# RHS_FEST22-EV_Logic.net
KiCad netlist of a schematic drawn in Altium Designer
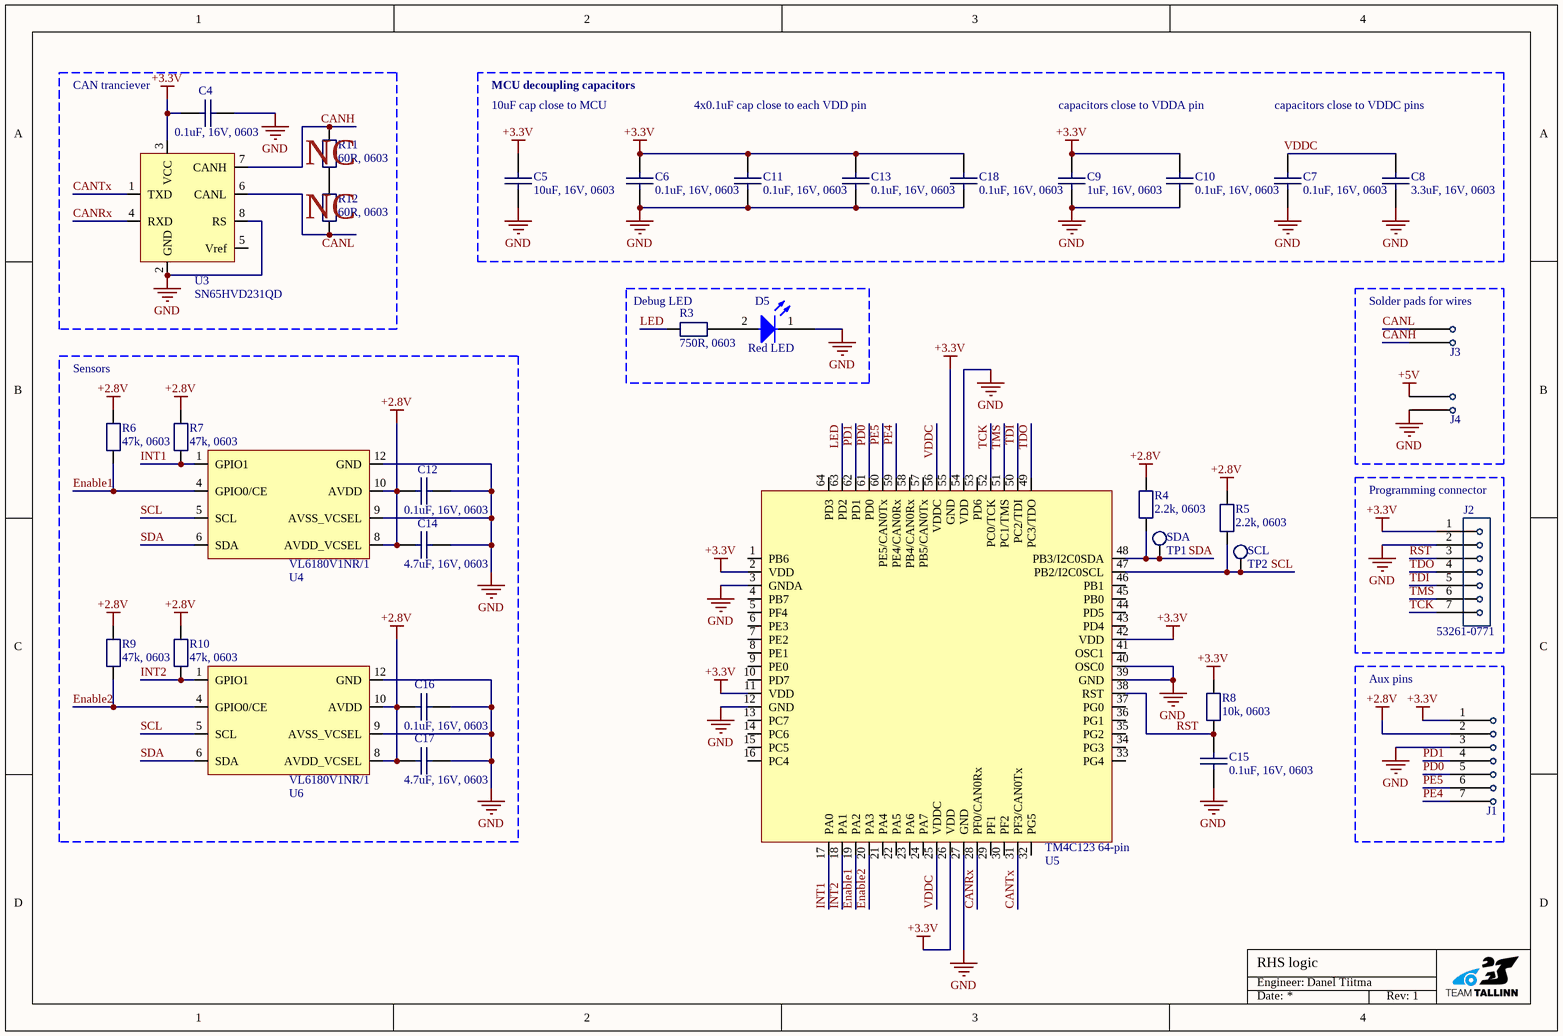
[diagram p0: RHS_FEST22-EV_Logic.SchDoc]

(export (version "E")
  (design (tool "Eeschema 10.0.6"))
  (components
    (comp (ref "C4")
      (value "0.1uF, 16V, 0603")
      (footprint "CAP [0603] 1608")
      (fields (field (name "MANUFACTURER") "MURATA"))
      (libsource (lib "RHS_FEST22-EV_Components") (part "Cap 0.1uF"))
    )
    (comp (ref "C5")
      (value "10uF, 16V, 0603")
      (footprint "CAP [0603] 1608")
      (fields (field (name "MANUFACTURER") "MURATA"))
      (libsource (lib "RHS_FEST22-EV_Components") (part "Cap 10uF"))
    )
    (comp (ref "C6")
      (value "0.1uF, 16V, 0603")
      (footprint "CAP [0603] 1608")
      (fields (field (name "MANUFACTURER") "MURATA"))
      (libsource (lib "RHS_FEST22-EV_Components") (part "Cap 0.1uF"))
    )
    (comp (ref "C7")
      (value "0.1uF, 16V, 0603")
      (footprint "CAP [0603] 1608")
      (fields (field (name "MANUFACTURER") "MURATA"))
      (libsource (lib "RHS_FEST22-EV_Components") (part "Cap 0.1uF"))
    )
    (comp (ref "C8")
      (value "3.3uF, 16V, 0603")
      (footprint "CAP [0603] 1608")
      (fields (field (name "MANUFACTURER") "TDK"))
      (libsource (lib "RHS_FEST22-EV_Components") (part "Cap 3.3uF"))
    )
    (comp (ref "C9")
      (value "1uF, 16V, 0603")
      (footprint "CAP [0603] 1608")
      (fields (field (name "MANUFACTURER") "MURATA"))
      (libsource (lib "RHS_FEST22-EV_Components") (part "Cap 1uF"))
    )
    (comp (ref "C10")
      (value "0.1uF, 16V, 0603")
      (footprint "CAP [0603] 1608")
      (fields (field (name "MANUFACTURER") "MURATA"))
      (libsource (lib "RHS_FEST22-EV_Components") (part "Cap 0.1uF"))
    )
    (comp (ref "C11")
      (value "0.1uF, 16V, 0603")
      (footprint "CAP [0603] 1608")
      (fields (field (name "MANUFACTURER") "MURATA"))
      (libsource (lib "RHS_FEST22-EV_Components") (part "Cap 0.1uF"))
    )
    (comp (ref "C12")
      (value "0.1uF, 16V, 0603")
      (footprint "CAP [0603] 1608")
      (fields (field (name "MANUFACTURER") "MURATA"))
      (libsource (lib "RHS_FEST22-EV_Components") (part "Cap 0.1uF"))
    )
    (comp (ref "C13")
      (value "0.1uF, 16V, 0603")
      (footprint "CAP [0603] 1608")
      (fields (field (name "MANUFACTURER") "MURATA"))
      (libsource (lib "RHS_FEST22-EV_Components") (part "Cap 0.1uF"))
    )
    (comp (ref "C14")
      (value "4.7uF, 16V, 0603")
      (footprint "FS_Footprints:CAP [0603] 1608")
      (fields (field (name "MANUFACTURER") "MURATA"))
      (libsource (lib "RHS_FEST22-EV_Components") (part "Cap 4.7uF"))
    )
    (comp (ref "C15")
      (value "0.1uF, 16V, 0603")
      (footprint "CAP [0603] 1608")
      (fields (field (name "MANUFACTURER") "MURATA"))
      (libsource (lib "RHS_FEST22-EV_Components") (part "Cap 0.1uF"))
    )
    (comp (ref "C16")
      (value "0.1uF, 16V, 0603")
      (footprint "CAP [0603] 1608")
      (fields (field (name "MANUFACTURER") "MURATA"))
      (libsource (lib "RHS_FEST22-EV_Components") (part "Cap 0.1uF"))
    )
    (comp (ref "C17")
      (value "4.7uF, 16V, 0603")
      (footprint "FS_Footprints:CAP [0603] 1608")
      (fields (field (name "MANUFACTURER") "MURATA"))
      (libsource (lib "RHS_FEST22-EV_Components") (part "Cap 4.7uF"))
    )
    (comp (ref "C18")
      (value "0.1uF, 16V, 0603")
      (footprint "CAP [0603] 1608")
      (fields (field (name "MANUFACTURER") "MURATA"))
      (libsource (lib "RHS_FEST22-EV_Components") (part "Cap 0.1uF"))
    )
    (comp (ref "D5")
      (value "Red LED")
      (footprint "LED [0603] 1608")
      (fields (field (name "MANUFACTURER") "KINGBRIGHT"))
      (libsource (lib "RHS_FEST22-EV_Components") (part "Red LED"))
    )
    (comp (ref "J1")
      (value "Wire connections_1")
      (footprint "Free pins")
      (description "Extra through holes")
      (libsource (lib "RHS_FEST22-EV_Components") (part "Wire connections_1"))
    )
    (comp (ref "J2")
      (value "53261-0771")
      (footprint "Molex 53261-0771")
      (description "Connector")
      (fields (field (name "MANUFACTURER") "Molex"))
      (libsource (lib "RHS_FEST22-EV_Components") (part "53261-0771"))
    )
    (comp (ref "J3")
      (value "Wire connections")
      (footprint "Wire pads")
      (libsource (lib "RHS_FEST22-EV_Components") (part "Wire connections"))
    )
    (comp (ref "J4")
      (value "Wire connections")
      (footprint "Wire pads")
      (libsource (lib "RHS_FEST22-EV_Components") (part "Wire connections"))
    )
    (comp (ref "R3")
      (value "750R, 0603")
      (footprint "RES [0603] 1608")
      (fields (field (name "MANUFACTURER") "YAGEO"))
      (libsource (lib "RHS_FEST22-EV_Components") (part "RES 750"))
    )
    (comp (ref "R4")
      (value "2.2k, 0603")
      (footprint "RES [0603] 1608")
      (fields (field (name "MANUFACTURER") "YAGEO"))
      (libsource (lib "RHS_FEST22-EV_Components") (part "Res 2.2k"))
    )
    (comp (ref "R5")
      (value "2.2k, 0603")
      (footprint "RES [0603] 1608")
      (fields (field (name "MANUFACTURER") "YAGEO"))
      (libsource (lib "RHS_FEST22-EV_Components") (part "Res 2.2k"))
    )
    (comp (ref "R6")
      (value "47k, 0603")
      (footprint "RES [0603] 1608")
      (fields (field (name "MANUFACTURER") "YAGEO"))
      (libsource (lib "RHS_FEST22-EV_Components") (part "Res 47k"))
    )
    (comp (ref "R7")
      (value "47k, 0603")
      (footprint "RES [0603] 1608")
      (fields (field (name "MANUFACTURER") "YAGEO"))
      (libsource (lib "RHS_FEST22-EV_Components") (part "Res 47k"))
    )
    (comp (ref "R8")
      (value "10k, 0603")
      (footprint "RES [0603] 1608")
      (fields (field (name "MANUFACTURER") "Yageo"))
      (libsource (lib "RHS_FEST22-EV_Components") (part "Res 10k"))
    )
    (comp (ref "R9")
      (value "47k, 0603")
      (footprint "RES [0603] 1608")
      (fields (field (name "MANUFACTURER") "YAGEO"))
      (libsource (lib "RHS_FEST22-EV_Components") (part "Res 47k"))
    )
    (comp (ref "R10")
      (value "47k, 0603")
      (footprint "RES [0603] 1608")
      (fields (field (name "MANUFACTURER") "YAGEO"))
      (libsource (lib "RHS_FEST22-EV_Components") (part "Res 47k"))
    )
    (comp (ref "R11")
      (value "60R, 0603")
      (footprint "FS_Footprints:RES [0603] 1608")
      (libsource (lib "FS_Components") (part "Resistor"))
    )
    (comp (ref "R12")
      (value "60R, 0603")
      (footprint "FS_Footprints:RES [0603] 1608")
      (libsource (lib "FS_Components") (part "Resistor"))
    )
    (comp (ref "TP1")
      (value "SDA")
      (footprint "FS_Footprints:Testpoint round 0.4mm")
      (libsource (lib "FS_Components") (part "Test Point"))
    )
    (comp (ref "TP2")
      (value "SCL")
      (footprint "FS_Footprints:Testpoint round 0.4mm")
      (libsource (lib "FS_Components") (part "Test Point"))
    )
    (comp (ref "U3")
      (value "SN65HVD231QD")
      (footprint "SOIC-8")
      (description "CAN tranciever")
      (fields (field (name "MANUFACTURER") "Texas Instruments"))
      (libsource (lib "RHS_FEST22-EV_Components") (part "SN65HVD231QD"))
    )
    (comp (ref "U4")
      (value "VL6180V1NR/1")
      (footprint "VL6180")
      (description "Time-of-Flight proximity sensor, 2.6V, 3V, Optical, RoHS")
      (fields (field (name "MANUFACTURER") "STMicroelectronics"))
      (libsource (lib "RHS_FEST22-EV_Components") (part "VL6180V1NR/1"))
    )
    (comp (ref "U5")
      (value "TM4C123 64-pin")
      (footprint "FS_Footprints:LQFP64")
      (description "MCU 32-Bit Tiva C ARM Cortex M4F RISC 256KB Flash 1.2V/3.3V 64-Pin LQFP Tray/Tube")
      (fields (field (name "MANUFACTURER") "Texas Instruments"))
      (libsource (lib "RHS_FEST22-EV_Components") (part "TM4C123 64-pin"))
    )
    (comp (ref "U6")
      (value "VL6180V1NR/1")
      (footprint "VL6180")
      (description "Time-of-Flight proximity sensor, 2.6V, 3V, Optical, RoHS")
      (fields (field (name "MANUFACTURER") "STMicroelectronics"))
      (libsource (lib "RHS_FEST22-EV_Components") (part "VL6180V1NR/1"))
    )
  )
  (nets
    (net (code "1") (name "+2.8V") (class "Default")
      (node (ref "C12") (pin "2") (pinfunction "2_2") (pintype "passive"))
      (node (ref "C14") (pin "2") (pinfunction "2_2") (pintype "passive"))
      (node (ref "C16") (pin "2") (pinfunction "2_2") (pintype "passive"))
      (node (ref "C17") (pin "2") (pinfunction "2_2") (pintype "passive"))
      (node (ref "J1") (pin "2") (pintype "passive"))
      (node (ref "R10") (pin "2") (pinfunction "2_2") (pintype "passive"))
      (node (ref "R4") (pin "2") (pinfunction "2_2") (pintype "passive"))
      (node (ref "R5") (pin "2") (pinfunction "2_2") (pintype "passive"))
      (node (ref "R6") (pin "2") (pinfunction "2_2") (pintype "passive"))
      (node (ref "R7") (pin "2") (pinfunction "2_2") (pintype "passive"))
      (node (ref "R9") (pin "2") (pinfunction "2_2") (pintype "passive"))
      (node (ref "U4") (pin "10") (pinfunction "AVDD_10") (pintype "passive"))
      (node (ref "U4") (pin "8") (pinfunction "AVDD_VCSEL_8") (pintype "passive"))
      (node (ref "U6") (pin "10") (pinfunction "AVDD_10") (pintype "passive"))
      (node (ref "U6") (pin "8") (pinfunction "AVDD_VCSEL_8") (pintype "passive"))
    )
    (net (code "2") (name "+3.3V") (class "Default")
      (node (ref "C10") (pin "1") (pinfunction "1_1") (pintype "passive"))
      (node (ref "C11") (pin "1") (pinfunction "1_1") (pintype "passive"))
      (node (ref "C13") (pin "1") (pinfunction "1_1") (pintype "passive"))
      (node (ref "C18") (pin "1") (pinfunction "1_1") (pintype "passive"))
      (node (ref "C4") (pin "2") (pinfunction "2_2") (pintype "passive"))
      (node (ref "C5") (pin "1") (pinfunction "1_1") (pintype "passive"))
      (node (ref "C6") (pin "2") (pinfunction "2_2") (pintype "passive"))
      (node (ref "C9") (pin "1") (pinfunction "1_1") (pintype "passive"))
      (node (ref "J1") (pin "1") (pintype "passive"))
      (node (ref "J2") (pin "1") (pinfunction "VCC_1") (pintype "passive"))
      (node (ref "R8") (pin "1") (pinfunction "1_1") (pintype "passive"))
      (node (ref "U3") (pin "3") (pinfunction "VCC_3") (pintype "passive"))
      (node (ref "U5") (pin "11") (pinfunction "VDD_11") (pintype "passive"))
      (node (ref "U5") (pin "2") (pinfunction "VDD_2") (pintype "passive"))
      (node (ref "U5") (pin "26") (pinfunction "VDD_26") (pintype "passive"))
      (node (ref "U5") (pin "42") (pinfunction "VDD_42") (pintype "passive"))
      (node (ref "U5") (pin "55") (pinfunction "GND_55") (pintype "passive"))
    )
    (net (code "3") (name "+5V") (class "Default")
      (node (ref "J4") (pin "1") (pinfunction "1_1") (pintype "passive"))
    )
    (net (code "4") (name "/CANH") (class "Default")
      (node (ref "J3") (pin "2") (pinfunction "2_2") (pintype "passive"))
      (node (ref "R11") (pin "2") (pinfunction "2_2") (pintype "passive"))
      (node (ref "U3") (pin "7") (pinfunction "CANH_7") (pintype "passive"))
    )
    (net (code "5") (name "/CANL") (class "Default")
      (node (ref "J3") (pin "1") (pinfunction "1_1") (pintype "passive"))
      (node (ref "R12") (pin "1") (pinfunction "1_1") (pintype "passive"))
      (node (ref "U3") (pin "6") (pinfunction "CANL_6") (pintype "passive"))
    )
    (net (code "6") (name "/CANRx") (class "Default")
      (node (ref "U3") (pin "4") (pinfunction "RXD_4") (pintype "passive"))
      (node (ref "U5") (pin "28") (pinfunction "PF0/CAN0Rx_28") (pintype "passive"))
    )
    (net (code "7") (name "/CANTx") (class "Default")
      (node (ref "U3") (pin "1") (pinfunction "TXD_1") (pintype "passive"))
      (node (ref "U5") (pin "31") (pinfunction "PF3/CAN0Tx_31") (pintype "passive"))
    )
    (net (code "8") (name "/Enable1") (class "Default")
      (node (ref "R6") (pin "1") (pinfunction "1_1") (pintype "passive"))
      (node (ref "U4") (pin "4") (pinfunction "GPIO0/CE_4") (pintype "passive"))
      (node (ref "U5") (pin "19") (pinfunction "PA2_19") (pintype "passive"))
    )
    (net (code "9") (name "/Enable2") (class "Default")
      (node (ref "R9") (pin "1") (pinfunction "1_1") (pintype "passive"))
      (node (ref "U5") (pin "20") (pinfunction "PA3_20") (pintype "passive"))
      (node (ref "U6") (pin "4") (pinfunction "GPIO0/CE_4") (pintype "passive"))
    )
    (net (code "10") (name "/INT1") (class "Default")
      (node (ref "R7") (pin "1") (pinfunction "1_1") (pintype "passive"))
      (node (ref "U4") (pin "1") (pinfunction "GPIO1_1") (pintype "passive"))
      (node (ref "U5") (pin "17") (pinfunction "PA0_17") (pintype "passive"))
    )
    (net (code "11") (name "/INT2") (class "Default")
      (node (ref "R10") (pin "1") (pinfunction "1_1") (pintype "passive"))
      (node (ref "U5") (pin "18") (pinfunction "PA1_18") (pintype "passive"))
      (node (ref "U6") (pin "1") (pinfunction "GPIO1_1") (pintype "passive"))
    )
    (net (code "12") (name "/LED") (class "Default")
      (node (ref "R3") (pin "2") (pinfunction "2_2") (pintype "passive"))
      (node (ref "U5") (pin "63") (pinfunction "PD2_63") (pintype "passive"))
    )
    (net (code "13") (name "/PD0") (class "Default")
      (node (ref "J1") (pin "5") (pintype "passive"))
      (node (ref "U5") (pin "61") (pinfunction "PD0_61") (pintype "passive"))
    )
    (net (code "14") (name "/PD1") (class "Default")
      (node (ref "J1") (pin "4") (pintype "passive"))
      (node (ref "U5") (pin "62") (pinfunction "PD1_62") (pintype "passive"))
    )
    (net (code "15") (name "/PE4") (class "Default")
      (node (ref "J1") (pin "7") (pintype "passive"))
      (node (ref "U5") (pin "59") (pinfunction "PE4/CAN0Rx_59") (pintype "passive"))
    )
    (net (code "16") (name "/PE5") (class "Default")
      (node (ref "J1") (pin "6") (pintype "passive"))
      (node (ref "U5") (pin "60") (pinfunction "PE5/CAN0Tx_60") (pintype "passive"))
    )
    (net (code "17") (name "/RST") (class "Default")
      (node (ref "C15") (pin "1") (pinfunction "1_1") (pintype "passive"))
      (node (ref "J2") (pin "3") (pinfunction "RST_3") (pintype "passive"))
      (node (ref "R8") (pin "2") (pinfunction "2_2") (pintype "passive"))
      (node (ref "U5") (pin "38") (pinfunction "RST_38") (pintype "passive"))
    )
    (net (code "18") (name "/SCL") (class "Default")
      (node (ref "R5") (pin "1") (pinfunction "1_1") (pintype "passive"))
      (node (ref "TP2") (pin "1") (pinfunction "TEST_1") (pintype "passive"))
      (node (ref "U4") (pin "5") (pinfunction "SCL_5") (pintype "passive"))
      (node (ref "U5") (pin "47") (pinfunction "PB2/I2C0SCL_47") (pintype "passive"))
      (node (ref "U6") (pin "5") (pinfunction "SCL_5") (pintype "passive"))
    )
    (net (code "19") (name "/SDA") (class "Default")
      (node (ref "R4") (pin "1") (pinfunction "1_1") (pintype "passive"))
      (node (ref "TP1") (pin "1") (pinfunction "TEST_1") (pintype "passive"))
      (node (ref "U4") (pin "6") (pinfunction "SDA_6") (pintype "passive"))
      (node (ref "U5") (pin "48") (pinfunction "PB3/I2C0SDA_48") (pintype "passive"))
      (node (ref "U6") (pin "6") (pinfunction "SDA_6") (pintype "passive"))
    )
    (net (code "20") (name "/TCK") (class "Default")
      (node (ref "J2") (pin "7") (pinfunction "TCK_7") (pintype "passive"))
      (node (ref "U5") (pin "52") (pinfunction "PC0/TCK_52") (pintype "passive"))
    )
    (net (code "21") (name "/TDI") (class "Default")
      (node (ref "J2") (pin "5") (pinfunction "TDI_5") (pintype "passive"))
      (node (ref "U5") (pin "50") (pinfunction "PC2/TDI_50") (pintype "passive"))
    )
    (net (code "22") (name "/TDO") (class "Default")
      (node (ref "J2") (pin "4") (pinfunction "TDO_4") (pintype "passive"))
      (node (ref "U5") (pin "49") (pinfunction "PC3/TDO_49") (pintype "passive"))
    )
    (net (code "23") (name "/TMS") (class "Default")
      (node (ref "J2") (pin "6") (pinfunction "TMS_6") (pintype "passive"))
      (node (ref "U5") (pin "51") (pinfunction "PC1/TMS_51") (pintype "passive"))
    )
    (net (code "24") (name "/VDDC") (class "Default")
      (node (ref "C7") (pin "2") (pinfunction "2_2") (pintype "passive"))
      (node (ref "C8") (pin "1") (pinfunction "1_1") (pintype "passive"))
      (node (ref "U5") (pin "25") (pinfunction "VDDC_25") (pintype "passive"))
      (node (ref "U5") (pin "56") (pinfunction "VDDC_56") (pintype "passive"))
    )
    (net (code "25") (name "GND") (class "Default")
      (node (ref "C10") (pin "2") (pinfunction "2_2") (pintype "passive"))
      (node (ref "C11") (pin "2") (pinfunction "2_2") (pintype "passive"))
      (node (ref "C12") (pin "1") (pinfunction "1_1") (pintype "passive"))
      (node (ref "C13") (pin "2") (pinfunction "2_2") (pintype "passive"))
      (node (ref "C14") (pin "1") (pinfunction "1_1") (pintype "passive"))
      (node (ref "C15") (pin "2") (pinfunction "2_2") (pintype "passive"))
      (node (ref "C16") (pin "1") (pinfunction "1_1") (pintype "passive"))
      (node (ref "C17") (pin "1") (pinfunction "1_1") (pintype "passive"))
      (node (ref "C18") (pin "2") (pinfunction "2_2") (pintype "passive"))
      (node (ref "C4") (pin "1") (pinfunction "1_1") (pintype "passive"))
      (node (ref "C5") (pin "2") (pinfunction "2_2") (pintype "passive"))
      (node (ref "C6") (pin "1") (pinfunction "1_1") (pintype "passive"))
      (node (ref "C7") (pin "1") (pinfunction "1_1") (pintype "passive"))
      (node (ref "C8") (pin "2") (pinfunction "2_2") (pintype "passive"))
      (node (ref "C9") (pin "2") (pinfunction "2_2") (pintype "passive"))
      (node (ref "D5") (pin "1") (pinfunction "A_1") (pintype "passive"))
      (node (ref "J1") (pin "3") (pintype "passive"))
      (node (ref "J2") (pin "2") (pinfunction "GND_2") (pintype "passive"))
      (node (ref "J4") (pin "2") (pinfunction "2_2") (pintype "passive"))
      (node (ref "U3") (pin "2") (pinfunction "GND_2") (pintype "passive"))
      (node (ref "U3") (pin "8") (pinfunction "RS_8") (pintype "passive"))
      (node (ref "U4") (pin "12") (pinfunction "GND_12") (pintype "passive"))
      (node (ref "U4") (pin "9") (pinfunction "AVSS_VCSEL_9") (pintype "passive"))
      (node (ref "U5") (pin "12") (pinfunction "GND_12") (pintype "passive"))
      (node (ref "U5") (pin "27") (pinfunction "GND_27") (pintype "passive"))
      (node (ref "U5") (pin "3") (pinfunction "GNDA_3") (pintype "passive"))
      (node (ref "U5") (pin "39") (pinfunction "GND_39") (pintype "passive"))
      (node (ref "U5") (pin "40") (pinfunction "OSC0_40") (pintype "passive"))
      (node (ref "U5") (pin "54") (pinfunction "VDD_54") (pintype "passive"))
      (node (ref "U6") (pin "12") (pinfunction "GND_12") (pintype "passive"))
      (node (ref "U6") (pin "9") (pinfunction "AVSS_VCSEL_9") (pintype "passive"))
    )
    (net (code "26") (name "Net-(D5-K)") (class "Default")
      (node (ref "D5") (pin "2") (pinfunction "K_2") (pintype "passive"))
      (node (ref "R3") (pin "1") (pinfunction "1_1") (pintype "passive"))
    )
    (net (code "27") (name "Net-(R11-Pad1)") (class "Default")
      (node (ref "R11") (pin "1") (pinfunction "1_1") (pintype "passive"))
      (node (ref "R12") (pin "2") (pinfunction "2_2") (pintype "passive"))
    )
    (net (code "28") (name "unconnected-(U3-Vref-Pad5)") (class "Default")
      (node (ref "U3") (pin "5") (pinfunction "Vref_5") (pintype "passive"))
    )
    (net (code "29") (name "unconnected-(U5-OSC1-Pad41)") (class "Default")
      (node (ref "U5") (pin "41") (pinfunction "OSC1_41") (pintype "passive"))
    )
    (net (code "30") (name "unconnected-(U5-PA4-Pad21)") (class "Default")
      (node (ref "U5") (pin "21") (pinfunction "PA4_21") (pintype "passive"))
    )
    (net (code "31") (name "unconnected-(U5-PA5-Pad22)") (class "Default")
      (node (ref "U5") (pin "22") (pinfunction "PA5_22") (pintype "passive"))
    )
    (net (code "32") (name "unconnected-(U5-PA6-Pad23)") (class "Default")
      (node (ref "U5") (pin "23") (pinfunction "PA6_23") (pintype "passive"))
    )
    (net (code "33") (name "unconnected-(U5-PA7-Pad24)") (class "Default")
      (node (ref "U5") (pin "24") (pinfunction "PA7_24") (pintype "passive"))
    )
    (net (code "34") (name "unconnected-(U5-PB0-Pad45)") (class "Default")
      (node (ref "U5") (pin "45") (pinfunction "PB0_45") (pintype "passive"))
    )
    (net (code "35") (name "unconnected-(U5-PB1-Pad46)") (class "Default")
      (node (ref "U5") (pin "46") (pinfunction "PB1_46") (pintype "passive"))
    )
    (net (code "36") (name "unconnected-(U5-PB4{slash}CAN0Rx-Pad58)") (class "Default")
      (node (ref "U5") (pin "58") (pinfunction "PB4/CAN0Rx_58") (pintype "passive"))
    )
    (net (code "37") (name "unconnected-(U5-PB5{slash}CAN0Tx-Pad57)") (class "Default")
      (node (ref "U5") (pin "57") (pinfunction "PB5/CAN0Tx_57") (pintype "passive"))
    )
    (net (code "38") (name "unconnected-(U5-PB6-Pad1)") (class "Default")
      (node (ref "U5") (pin "1") (pinfunction "PB6_1") (pintype "passive"))
    )
    (net (code "39") (name "unconnected-(U5-PB7-Pad4)") (class "Default")
      (node (ref "U5") (pin "4") (pinfunction "PB7_4") (pintype "passive"))
    )
    (net (code "40") (name "unconnected-(U5-PC4-Pad16)") (class "Default")
      (node (ref "U5") (pin "16") (pinfunction "PC4_16") (pintype "passive"))
    )
    (net (code "41") (name "unconnected-(U5-PC5-Pad15)") (class "Default")
      (node (ref "U5") (pin "15") (pinfunction "PC5_15") (pintype "passive"))
    )
    (net (code "42") (name "unconnected-(U5-PC6-Pad14)") (class "Default")
      (node (ref "U5") (pin "14") (pinfunction "PC6_14") (pintype "passive"))
    )
    (net (code "43") (name "unconnected-(U5-PC7-Pad13)") (class "Default")
      (node (ref "U5") (pin "13") (pinfunction "PC7_13") (pintype "passive"))
    )
    (net (code "44") (name "unconnected-(U5-PD3-Pad64)") (class "Default")
      (node (ref "U5") (pin "64") (pinfunction "PD3_64") (pintype "passive"))
    )
    (net (code "45") (name "unconnected-(U5-PD4-Pad43)") (class "Default")
      (node (ref "U5") (pin "43") (pinfunction "PD4_43") (pintype "passive"))
    )
    (net (code "46") (name "unconnected-(U5-PD5-Pad44)") (class "Default")
      (node (ref "U5") (pin "44") (pinfunction "PD5_44") (pintype "passive"))
    )
    (net (code "47") (name "unconnected-(U5-PD6-Pad53)") (class "Default")
      (node (ref "U5") (pin "53") (pinfunction "PD6_53") (pintype "passive"))
    )
    (net (code "48") (name "unconnected-(U5-PD7-Pad10)") (class "Default")
      (node (ref "U5") (pin "10") (pinfunction "PD7_10") (pintype "passive"))
    )
    (net (code "49") (name "unconnected-(U5-PE0-Pad9)") (class "Default")
      (node (ref "U5") (pin "9") (pinfunction "PE0_9") (pintype "passive"))
    )
    (net (code "50") (name "unconnected-(U5-PE1-Pad8)") (class "Default")
      (node (ref "U5") (pin "8") (pinfunction "PE1_8") (pintype "passive"))
    )
    (net (code "51") (name "unconnected-(U5-PE2-Pad7)") (class "Default")
      (node (ref "U5") (pin "7") (pinfunction "PE2_7") (pintype "passive"))
    )
    (net (code "52") (name "unconnected-(U5-PE3-Pad6)") (class "Default")
      (node (ref "U5") (pin "6") (pinfunction "PE3_6") (pintype "passive"))
    )
    (net (code "53") (name "unconnected-(U5-PF1-Pad29)") (class "Default")
      (node (ref "U5") (pin "29") (pinfunction "PF1_29") (pintype "passive"))
    )
    (net (code "54") (name "unconnected-(U5-PF2-Pad30)") (class "Default")
      (node (ref "U5") (pin "30") (pinfunction "PF2_30") (pintype "passive"))
    )
    (net (code "55") (name "unconnected-(U5-PF4-Pad5)") (class "Default")
      (node (ref "U5") (pin "5") (pinfunction "PF4_5") (pintype "passive"))
    )
    (net (code "56") (name "unconnected-(U5-PG0-Pad37)") (class "Default")
      (node (ref "U5") (pin "37") (pinfunction "PG0_37") (pintype "passive"))
    )
    (net (code "57") (name "unconnected-(U5-PG1-Pad36)") (class "Default")
      (node (ref "U5") (pin "36") (pinfunction "PG1_36") (pintype "passive"))
    )
    (net (code "58") (name "unconnected-(U5-PG2-Pad35)") (class "Default")
      (node (ref "U5") (pin "35") (pinfunction "PG2_35") (pintype "passive"))
    )
    (net (code "59") (name "unconnected-(U5-PG3-Pad34)") (class "Default")
      (node (ref "U5") (pin "34") (pinfunction "PG3_34") (pintype "passive"))
    )
    (net (code "60") (name "unconnected-(U5-PG4-Pad33)") (class "Default")
      (node (ref "U5") (pin "33") (pinfunction "PG4_33") (pintype "passive"))
    )
    (net (code "61") (name "unconnected-(U5-PG5-Pad32)") (class "Default")
      (node (ref "U5") (pin "32") (pinfunction "PG5_32") (pintype "passive"))
    )
  )
)
